# GaN_Schaltnetzteil.net
KiCad netlist of a schematic drawn in EAGLE
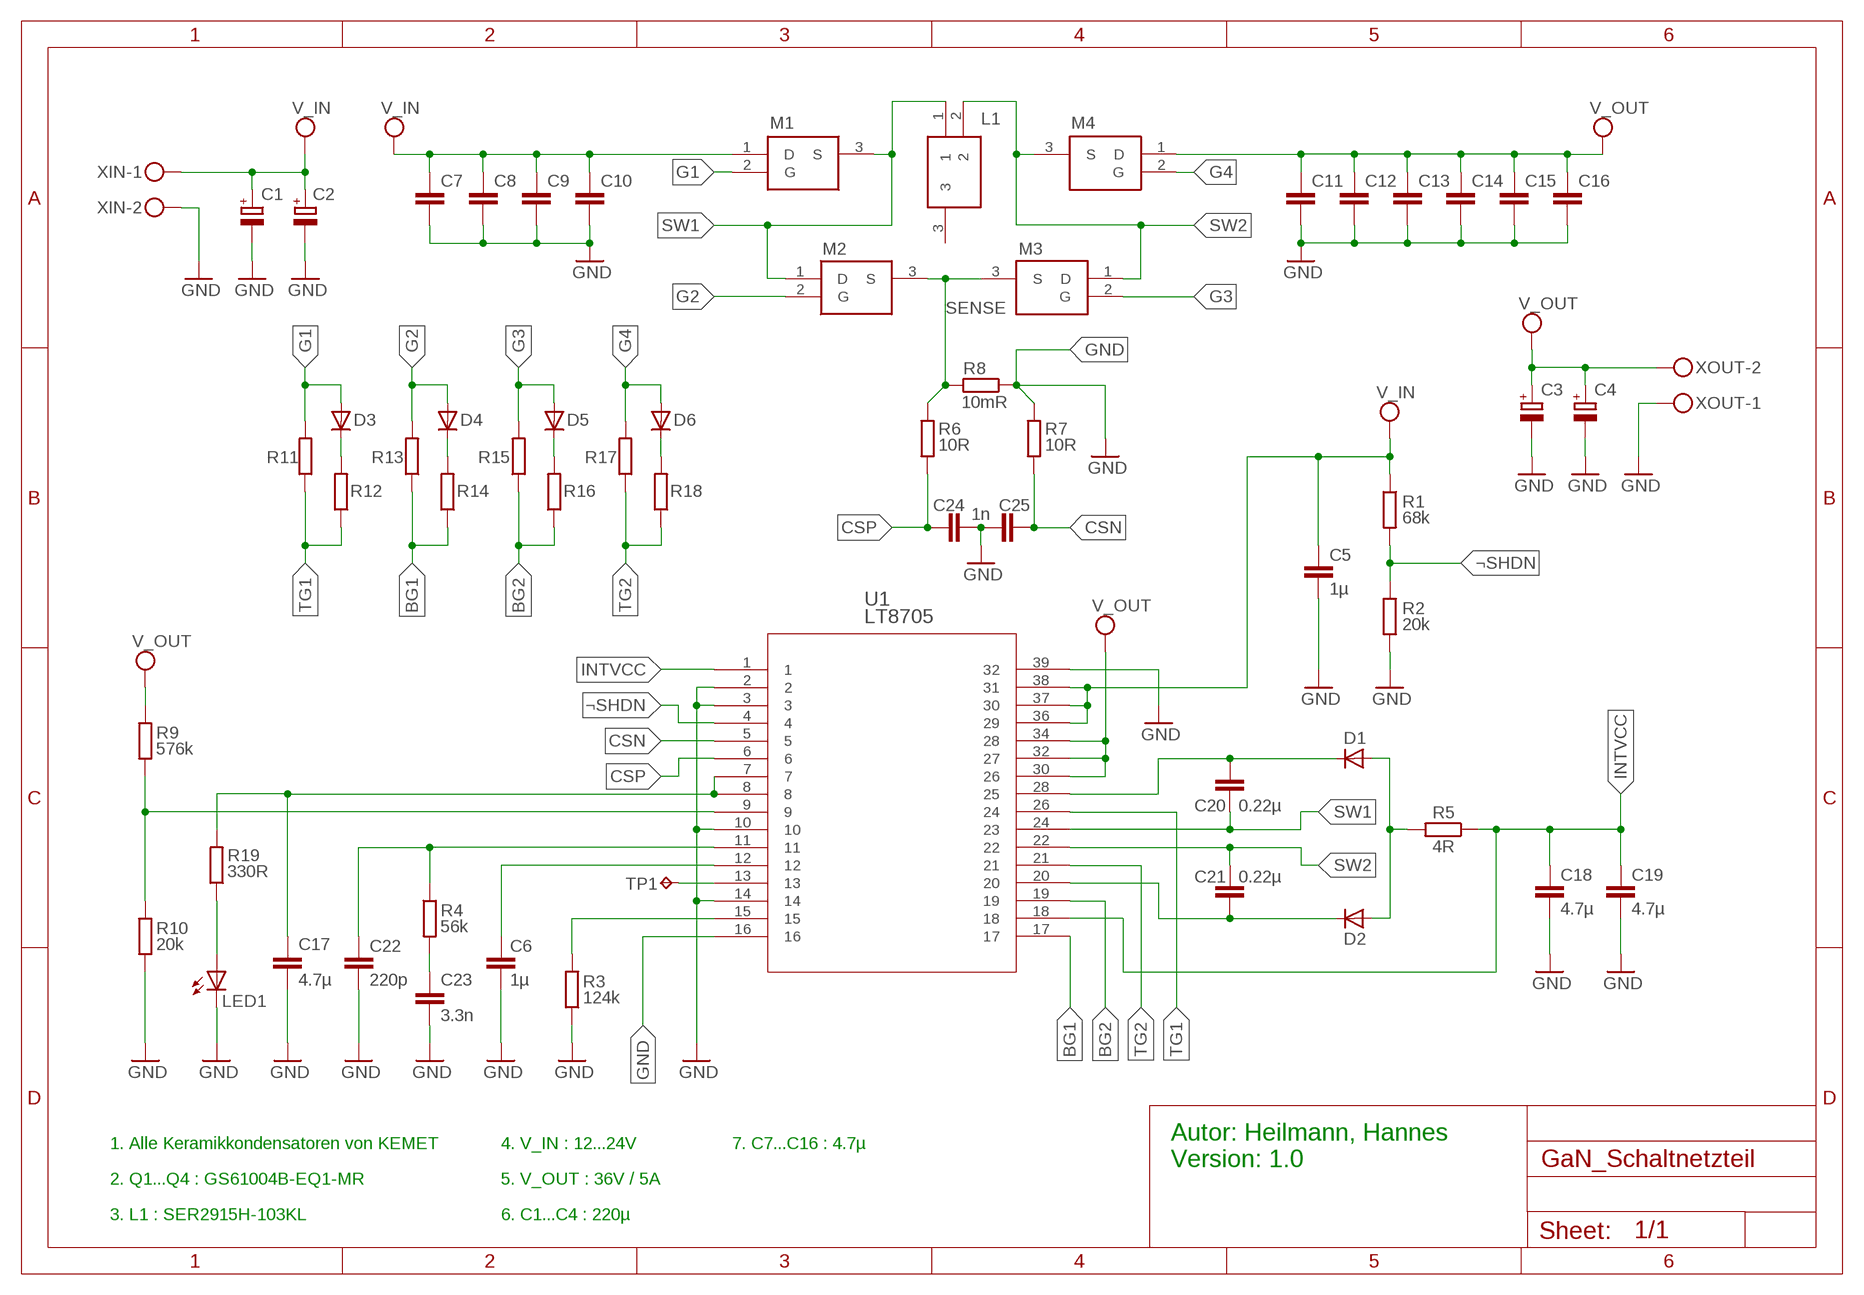
[diagram p0: schematic, sheet 1]

(export (version "E")
  (design (tool "Eeschema 10.0.6"))
  (components
    (comp (ref "C1")
      (value "220µ")
      (footprint "eagle-import:PANASONIC_G")
      (libsource (lib "eagle-import") (part "CPOL-EUG"))
    )
    (comp (ref "C2")
      (value "220µ")
      (footprint "eagle-import:PANASONIC_G")
      (libsource (lib "eagle-import") (part "CPOL-EUG"))
    )
    (comp (ref "C3")
      (value "220µ")
      (footprint "eagle-import:PANASONIC_G")
      (libsource (lib "eagle-import") (part "CPOL-EUG"))
    )
    (comp (ref "C4")
      (value "220µ")
      (footprint "eagle-import:PANASONIC_G")
      (libsource (lib "eagle-import") (part "CPOL-EUG"))
    )
    (comp (ref "C5")
      (value "1µ")
      (footprint "eagle-import:C1206K")
      (libsource (lib "eagle-import") (part "C-EUC1206K"))
    )
    (comp (ref "C6")
      (value "1µ")
      (footprint "eagle-import:C1206K")
      (libsource (lib "eagle-import") (part "C-EUC1206K"))
    )
    (comp (ref "C7")
      (value "4.7µ")
      (footprint "eagle-import:C1206K")
      (libsource (lib "eagle-import") (part "C-EUC1206K"))
    )
    (comp (ref "C8")
      (value "4.7µ")
      (footprint "eagle-import:C1206K")
      (libsource (lib "eagle-import") (part "C-EUC1206K"))
    )
    (comp (ref "C9")
      (value "4.7µ")
      (footprint "eagle-import:C1206K")
      (libsource (lib "eagle-import") (part "C-EUC1206K"))
    )
    (comp (ref "C10")
      (value "4.7µ")
      (footprint "eagle-import:C1206K")
      (libsource (lib "eagle-import") (part "C-EUC1206K"))
    )
    (comp (ref "C11")
      (value "4.7µ")
      (footprint "eagle-import:C1206K")
      (libsource (lib "eagle-import") (part "C-EUC1206K"))
    )
    (comp (ref "C12")
      (value "4.7µ")
      (footprint "eagle-import:C1206K")
      (libsource (lib "eagle-import") (part "C-EUC1206K"))
    )
    (comp (ref "C13")
      (value "4.7µ")
      (footprint "eagle-import:C1206K")
      (libsource (lib "eagle-import") (part "C-EUC1206K"))
    )
    (comp (ref "C14")
      (value "4.7µ")
      (footprint "eagle-import:C1206K")
      (libsource (lib "eagle-import") (part "C-EUC1206K"))
    )
    (comp (ref "C15")
      (value "4.7µ")
      (footprint "eagle-import:C1206K")
      (libsource (lib "eagle-import") (part "C-EUC1206K"))
    )
    (comp (ref "C16")
      (value "4.7µ")
      (footprint "eagle-import:C1206K")
      (libsource (lib "eagle-import") (part "C-EUC1206K"))
    )
    (comp (ref "C17")
      (value "4.7µ")
      (footprint "eagle-import:C1206K")
      (libsource (lib "eagle-import") (part "C-EUC1206K"))
    )
    (comp (ref "C18")
      (value "4.7µ")
      (footprint "eagle-import:C1206K")
      (libsource (lib "eagle-import") (part "C-EUC1206K"))
    )
    (comp (ref "C19")
      (value "4.7µ")
      (footprint "eagle-import:C1206K")
      (libsource (lib "eagle-import") (part "C-EUC1206K"))
    )
    (comp (ref "C20")
      (value "0.22µ")
      (footprint "eagle-import:C1206K")
      (libsource (lib "eagle-import") (part "C-EUC1206K"))
    )
    (comp (ref "C21")
      (value "0.22µ")
      (footprint "eagle-import:C1206K")
      (libsource (lib "eagle-import") (part "C-EUC1206K"))
    )
    (comp (ref "C22")
      (value "220p")
      (footprint "eagle-import:C1206K")
      (libsource (lib "eagle-import") (part "C-EUC1206K"))
    )
    (comp (ref "C23")
      (value "3.3n")
      (footprint "eagle-import:C1206K")
      (libsource (lib "eagle-import") (part "C-EUC1206K"))
    )
    (comp (ref "C24")
      (value "1n")
      (footprint "eagle-import:C1206K")
      (libsource (lib "eagle-import") (part "C-EUC1206K"))
    )
    (comp (ref "C25")
      (value "1n")
      (footprint "eagle-import:C1206K")
      (libsource (lib "eagle-import") (part "C-EUC1206K"))
    )
    (comp (ref "D1")
      (value "GF1")
      (footprint "eagle-import:SMA-DO214AC")
      (fields (field (name "SPICEPREFIX") "D"))
      (libsource (lib "eagle-import") (part "GF1"))
    )
    (comp (ref "D2")
      (value "GF1")
      (footprint "eagle-import:SMA-DO214AC")
      (libsource (lib "eagle-import") (part "GF1"))
    )
    (comp (ref "D3")
      (value "GF1")
      (footprint "eagle-import:SMA-DO214AC")
      (libsource (lib "eagle-import") (part "GF1"))
    )
    (comp (ref "D4")
      (value "GF1")
      (footprint "eagle-import:SMA-DO214AC")
      (libsource (lib "eagle-import") (part "GF1"))
    )
    (comp (ref "D5")
      (value "GF1")
      (footprint "eagle-import:SMA-DO214AC")
      (libsource (lib "eagle-import") (part "GF1"))
    )
    (comp (ref "D6")
      (value "GF1")
      (footprint "eagle-import:SMA-DO214AC")
      (libsource (lib "eagle-import") (part "GF1"))
    )
    (comp (ref "L1")
      (value "SER2915H-103KL")
      (footprint "eagle-import:SER2900")
      (fields (field (name "FARNELL_PART_NUMBER") "2288897"))
      (libsource (lib "eagle-import") (part "SER2915H-103KL"))
    )
    (comp (ref "LED1")
      (value "LEDSMT1206")
      (footprint "eagle-import:1206")
      (libsource (lib "eagle-import") (part "LEDSMT1206"))
    )
    (comp (ref "M1")
      (value "GS61004B-E01-MR")
      (footprint "eagle-import:GS61004B-E01-MR")
      (fields (field (name "MOUSER_PART_NUMBER") "499-GS61004B-E01-MR"))
      (libsource (lib "eagle-import") (part "GS61004B-E01-MR"))
    )
    (comp (ref "M2")
      (value "GS61004B-E01-MR")
      (footprint "eagle-import:GS61004B-E01-MR")
      (fields (field (name "MOUSER_PART_NUMBER") "499-GS61004B-E01-MR"))
      (libsource (lib "eagle-import") (part "GS61004B-E01-MR"))
    )
    (comp (ref "M3")
      (value "GS61004B-E01-MR")
      (footprint "eagle-import:GS61004B-E01-MR")
      (fields (field (name "MOUSER_PART_NUMBER") "499-GS61004B-E01-MR"))
      (libsource (lib "eagle-import") (part "GS61004B-E01-MR"))
    )
    (comp (ref "M4")
      (value "GS61004B-E01-MR")
      (footprint "eagle-import:GS61004B-E01-MR")
      (fields (field (name "MOUSER_PART_NUMBER") "499-GS61004B-E01-MR"))
      (libsource (lib "eagle-import") (part "GS61004B-E01-MR"))
    )
    (comp (ref "R1")
      (value "68k")
      (footprint "eagle-import:R1206")
      (libsource (lib "eagle-import") (part "R-EU_R1206"))
    )
    (comp (ref "R2")
      (value "20k")
      (footprint "eagle-import:R1206")
      (libsource (lib "eagle-import") (part "R-EU_R1206"))
    )
    (comp (ref "R3")
      (value "124k")
      (footprint "eagle-import:R1206")
      (libsource (lib "eagle-import") (part "R-EU_R1206"))
    )
    (comp (ref "R4")
      (value "56k")
      (footprint "eagle-import:R1206")
      (libsource (lib "eagle-import") (part "R-EU_R1206"))
    )
    (comp (ref "R5")
      (value "4R")
      (footprint "eagle-import:R1206")
      (libsource (lib "eagle-import") (part "R-EU_R1206"))
    )
    (comp (ref "R6")
      (value "10R")
      (footprint "eagle-import:R1206")
      (libsource (lib "eagle-import") (part "R-EU_R1206"))
    )
    (comp (ref "R7")
      (value "10R")
      (footprint "eagle-import:R1206")
      (libsource (lib "eagle-import") (part "R-EU_R1206"))
    )
    (comp (ref "R8")
      (value "10mR")
      (footprint "eagle-import:R1206")
      (libsource (lib "eagle-import") (part "R-EU_R1206"))
    )
    (comp (ref "R9")
      (value "576k")
      (footprint "eagle-import:R1206")
      (libsource (lib "eagle-import") (part "R-EU_R1206"))
    )
    (comp (ref "R10")
      (value "20k")
      (footprint "eagle-import:R1206")
      (libsource (lib "eagle-import") (part "R-EU_R1206"))
    )
    (comp (ref "R11")
      (value "R-EU_R1206")
      (footprint "eagle-import:R1206")
      (libsource (lib "eagle-import") (part "R-EU_R1206"))
    )
    (comp (ref "R12")
      (value "R-EU_R1206")
      (footprint "eagle-import:R1206")
      (libsource (lib "eagle-import") (part "R-EU_R1206"))
    )
    (comp (ref "R13")
      (value "R-EU_R1206")
      (footprint "eagle-import:R1206")
      (libsource (lib "eagle-import") (part "R-EU_R1206"))
    )
    (comp (ref "R14")
      (value "R-EU_R1206")
      (footprint "eagle-import:R1206")
      (libsource (lib "eagle-import") (part "R-EU_R1206"))
    )
    (comp (ref "R15")
      (value "R-EU_R1206")
      (footprint "eagle-import:R1206")
      (libsource (lib "eagle-import") (part "R-EU_R1206"))
    )
    (comp (ref "R16")
      (value "R-EU_R1206")
      (footprint "eagle-import:R1206")
      (libsource (lib "eagle-import") (part "R-EU_R1206"))
    )
    (comp (ref "R17")
      (value "R-EU_R1206")
      (footprint "eagle-import:R1206")
      (libsource (lib "eagle-import") (part "R-EU_R1206"))
    )
    (comp (ref "R18")
      (value "R-EU_R1206")
      (footprint "eagle-import:R1206")
      (libsource (lib "eagle-import") (part "R-EU_R1206"))
    )
    (comp (ref "R19")
      (value "330R")
      (footprint "eagle-import:R1206")
      (libsource (lib "eagle-import") (part "R-EU_R1206"))
    )
    (comp (ref "TP1")
      (value "TPTP08R")
      (footprint "eagle-import:TP08R")
      (libsource (lib "eagle-import") (part "TPTP08R"))
    )
    (comp (ref "U1")
      (value "LT8705")
      (footprint "eagle-import:TSSOP-38_FE_AB")
      (libsource (lib "eagle-import") (part "LT8705"))
    )
    (comp (ref "XIN")
      (value "INPUT")
      (footprint "eagle-import:W237-102")
      (fields (field (name "MPN") "237-102"))
      (libsource (lib "eagle-import") (part "W237-102"))
    )
    (comp (ref "XOUT")
      (value "OUTPUT")
      (footprint "eagle-import:W237-102")
      (fields (field (name "MPN") "237-102"))
      (libsource (lib "eagle-import") (part "W237-102"))
    )
  )
  (nets
    (net (code "1") (name "/SENSE") (class "Default")
      (node (ref "M2") (pin "3") (pinfunction "S_3") (pintype "bidirectional"))
      (node (ref "M3") (pin "3") (pinfunction "S_3") (pintype "bidirectional"))
      (node (ref "R6") (pin "2") (pinfunction "2_2") (pintype "passive"))
      (node (ref "R8") (pin "2") (pinfunction "2_2") (pintype "passive"))
    )
    (net (code "2") (name "BG1") (class "Default")
      (node (ref "R13") (pin "1") (pinfunction "1_1") (pintype "passive"))
      (node (ref "R14") (pin "1") (pinfunction "1_1") (pintype "passive"))
      (node (ref "U1") (pin "17") (pinfunction "17_17") (pintype "passive"))
    )
    (net (code "3") (name "BG2") (class "Default")
      (node (ref "R15") (pin "1") (pinfunction "1_1") (pintype "passive"))
      (node (ref "R16") (pin "1") (pinfunction "1_1") (pintype "passive"))
      (node (ref "U1") (pin "19") (pinfunction "19_19") (pintype "passive"))
    )
    (net (code "4") (name "CSN") (class "Default")
      (node (ref "C25") (pin "2") (pinfunction "2_2") (pintype "passive"))
      (node (ref "R7") (pin "1") (pinfunction "1_1") (pintype "passive"))
      (node (ref "U1") (pin "5") (pinfunction "5_5") (pintype "passive"))
    )
    (net (code "5") (name "CSP") (class "Default")
      (node (ref "C24") (pin "1") (pinfunction "1_1") (pintype "passive"))
      (node (ref "R6") (pin "1") (pinfunction "1_1") (pintype "passive"))
      (node (ref "U1") (pin "6") (pinfunction "6_6") (pintype "passive"))
    )
    (net (code "6") (name "G1") (class "Default")
      (node (ref "D3") (pin "A") (pinfunction "A_A") (pintype "passive"))
      (node (ref "M1") (pin "2") (pinfunction "G_2") (pintype "bidirectional"))
      (node (ref "R11") (pin "2") (pinfunction "2_2") (pintype "passive"))
    )
    (net (code "7") (name "G2") (class "Default")
      (node (ref "D4") (pin "A") (pinfunction "A_A") (pintype "passive"))
      (node (ref "M2") (pin "2") (pinfunction "G_2") (pintype "bidirectional"))
      (node (ref "R13") (pin "2") (pinfunction "2_2") (pintype "passive"))
    )
    (net (code "8") (name "G3") (class "Default")
      (node (ref "D5") (pin "A") (pinfunction "A_A") (pintype "passive"))
      (node (ref "M3") (pin "2") (pinfunction "G_2") (pintype "bidirectional"))
      (node (ref "R15") (pin "2") (pinfunction "2_2") (pintype "passive"))
    )
    (net (code "9") (name "G4") (class "Default")
      (node (ref "D6") (pin "A") (pinfunction "A_A") (pintype "passive"))
      (node (ref "M4") (pin "2") (pinfunction "G_2") (pintype "bidirectional"))
      (node (ref "R17") (pin "2") (pinfunction "2_2") (pintype "passive"))
    )
    (net (code "10") (name "GND") (class "Default")
      (node (ref "C1") (pin "-") (pinfunction "-_-") (pintype "passive"))
      (node (ref "C10") (pin "2") (pinfunction "2_2") (pintype "passive"))
      (node (ref "C11") (pin "2") (pinfunction "2_2") (pintype "passive"))
      (node (ref "C12") (pin "2") (pinfunction "2_2") (pintype "passive"))
      (node (ref "C13") (pin "2") (pinfunction "2_2") (pintype "passive"))
      (node (ref "C14") (pin "2") (pinfunction "2_2") (pintype "passive"))
      (node (ref "C15") (pin "2") (pinfunction "2_2") (pintype "passive"))
      (node (ref "C16") (pin "2") (pinfunction "2_2") (pintype "passive"))
      (node (ref "C17") (pin "2") (pinfunction "2_2") (pintype "passive"))
      (node (ref "C18") (pin "2") (pinfunction "2_2") (pintype "passive"))
      (node (ref "C19") (pin "2") (pinfunction "2_2") (pintype "passive"))
      (node (ref "C2") (pin "-") (pinfunction "-_-") (pintype "passive"))
      (node (ref "C22") (pin "2") (pinfunction "2_2") (pintype "passive"))
      (node (ref "C23") (pin "2") (pinfunction "2_2") (pintype "passive"))
      (node (ref "C24") (pin "2") (pinfunction "2_2") (pintype "passive"))
      (node (ref "C25") (pin "1") (pinfunction "1_1") (pintype "passive"))
      (node (ref "C3") (pin "-") (pinfunction "-_-") (pintype "passive"))
      (node (ref "C4") (pin "-") (pinfunction "-_-") (pintype "passive"))
      (node (ref "C5") (pin "2") (pinfunction "2_2") (pintype "passive"))
      (node (ref "C6") (pin "2") (pinfunction "2_2") (pintype "passive"))
      (node (ref "C7") (pin "2") (pinfunction "2_2") (pintype "passive"))
      (node (ref "C8") (pin "2") (pinfunction "2_2") (pintype "passive"))
      (node (ref "C9") (pin "2") (pinfunction "2_2") (pintype "passive"))
      (node (ref "LED1") (pin "C") (pinfunction "C_C") (pintype "passive"))
      (node (ref "R10") (pin "2") (pinfunction "2_2") (pintype "passive"))
      (node (ref "R2") (pin "2") (pinfunction "2_2") (pintype "passive"))
      (node (ref "R3") (pin "1") (pinfunction "1_1") (pintype "passive"))
      (node (ref "R7") (pin "2") (pinfunction "2_2") (pintype "passive"))
      (node (ref "R8") (pin "1") (pinfunction "1_1") (pintype "passive"))
      (node (ref "U1") (pin "10") (pinfunction "10_10") (pintype "passive"))
      (node (ref "U1") (pin "14") (pinfunction "14_14") (pintype "passive"))
      (node (ref "U1") (pin "16") (pinfunction "16_16") (pintype "passive"))
      (node (ref "U1") (pin "2") (pinfunction "2_2") (pintype "passive"))
      (node (ref "U1") (pin "3") (pinfunction "3_3") (pintype "passive"))
      (node (ref "U1") (pin "39") (pinfunction "32_39") (pintype "passive"))
      (node (ref "XIN") (pin "2") (pinfunction "KL_2") (pintype "passive"))
      (node (ref "XOUT") (pin "1") (pinfunction "KL_1") (pintype "passive"))
    )
    (net (code "11") (name "INTVCC") (class "Default")
      (node (ref "C18") (pin "1") (pinfunction "1_1") (pintype "passive"))
      (node (ref "C19") (pin "1") (pinfunction "1_1") (pintype "passive"))
      (node (ref "R5") (pin "1") (pinfunction "1_1") (pintype "passive"))
      (node (ref "U1") (pin "1") (pinfunction "1_1") (pintype "passive"))
      (node (ref "U1") (pin "18") (pinfunction "18_18") (pintype "passive"))
    )
    (net (code "12") (name "Net-(C6-Pad1)") (class "Default")
      (node (ref "C6") (pin "1") (pinfunction "1_1") (pintype "passive"))
      (node (ref "U1") (pin "12") (pinfunction "12_12") (pintype "passive"))
    )
    (net (code "13") (name "Net-(C17-Pad1)") (class "Default")
      (node (ref "C17") (pin "1") (pinfunction "1_1") (pintype "passive"))
      (node (ref "R19") (pin "2") (pinfunction "2_2") (pintype "passive"))
      (node (ref "U1") (pin "7") (pinfunction "7_7") (pintype "passive"))
      (node (ref "U1") (pin "8") (pinfunction "8_8") (pintype "passive"))
    )
    (net (code "14") (name "Net-(C22-Pad1)") (class "Default")
      (node (ref "C22") (pin "1") (pinfunction "1_1") (pintype "passive"))
      (node (ref "R4") (pin "1") (pinfunction "1_1") (pintype "passive"))
      (node (ref "U1") (pin "11") (pinfunction "11_11") (pintype "passive"))
    )
    (net (code "15") (name "Net-(C23-Pad1)") (class "Default")
      (node (ref "C23") (pin "1") (pinfunction "1_1") (pintype "passive"))
      (node (ref "R4") (pin "2") (pinfunction "2_2") (pintype "passive"))
    )
    (net (code "16") (name "Net-(D1-C)") (class "Default")
      (node (ref "C20") (pin "1") (pinfunction "1_1") (pintype "passive"))
      (node (ref "D1") (pin "K") (pinfunction "C_K") (pintype "passive"))
      (node (ref "U1") (pin "28") (pinfunction "25_28") (pintype "passive"))
    )
    (net (code "17") (name "Net-(D1-PadA)") (class "Default")
      (node (ref "D1") (pin "A") (pinfunction "A_A") (pintype "passive"))
      (node (ref "D2") (pin "A") (pinfunction "A_A") (pintype "passive"))
      (node (ref "R5") (pin "2") (pinfunction "2_2") (pintype "passive"))
    )
    (net (code "18") (name "Net-(D2-C)") (class "Default")
      (node (ref "C21") (pin "1") (pinfunction "1_1") (pintype "passive"))
      (node (ref "D2") (pin "K") (pinfunction "C_K") (pintype "passive"))
      (node (ref "U1") (pin "20") (pinfunction "20_20") (pintype "passive"))
    )
    (net (code "19") (name "Net-(D3-C)") (class "Default")
      (node (ref "D3") (pin "K") (pinfunction "C_K") (pintype "passive"))
      (node (ref "R12") (pin "2") (pinfunction "2_2") (pintype "passive"))
    )
    (net (code "20") (name "Net-(D4-C)") (class "Default")
      (node (ref "D4") (pin "K") (pinfunction "C_K") (pintype "passive"))
      (node (ref "R14") (pin "2") (pinfunction "2_2") (pintype "passive"))
    )
    (net (code "21") (name "Net-(D5-C)") (class "Default")
      (node (ref "D5") (pin "K") (pinfunction "C_K") (pintype "passive"))
      (node (ref "R16") (pin "2") (pinfunction "2_2") (pintype "passive"))
    )
    (net (code "22") (name "Net-(D6-C)") (class "Default")
      (node (ref "D6") (pin "K") (pinfunction "C_K") (pintype "passive"))
      (node (ref "R18") (pin "2") (pinfunction "2_2") (pintype "passive"))
    )
    (net (code "23") (name "Net-(LED1-PadA)") (class "Default")
      (node (ref "LED1") (pin "A") (pinfunction "A_A") (pintype "passive"))
      (node (ref "R19") (pin "1") (pinfunction "1_1") (pintype "passive"))
    )
    (net (code "24") (name "Net-(R3-Pad2)") (class "Default")
      (node (ref "R3") (pin "2") (pinfunction "2_2") (pintype "passive"))
      (node (ref "U1") (pin "15") (pinfunction "15_15") (pintype "passive"))
    )
    (net (code "25") (name "Net-(R10-Pad1)") (class "Default")
      (node (ref "R10") (pin "1") (pinfunction "1_1") (pintype "passive"))
      (node (ref "R9") (pin "2") (pinfunction "2_2") (pintype "passive"))
      (node (ref "U1") (pin "9") (pinfunction "9_9") (pintype "passive"))
    )
    (net (code "26") (name "Net-(TP1-PadTP)") (class "Default")
      (node (ref "TP1") (pin "TP") (pinfunction "TP_TP") (pintype "input"))
      (node (ref "U1") (pin "13") (pinfunction "13_13") (pintype "passive"))
    )
    (net (code "27") (name "SW1") (class "Default")
      (node (ref "C20") (pin "2") (pinfunction "2_2") (pintype "passive"))
      (node (ref "L1") (pin "1") (pinfunction "1_1") (pintype "bidirectional"))
      (node (ref "M1") (pin "3") (pinfunction "S_3") (pintype "bidirectional"))
      (node (ref "M2") (pin "1") (pinfunction "D_1") (pintype "bidirectional"))
      (node (ref "U1") (pin "24") (pinfunction "23_24") (pintype "passive"))
    )
    (net (code "28") (name "SW2") (class "Default")
      (node (ref "C21") (pin "2") (pinfunction "2_2") (pintype "passive"))
      (node (ref "L1") (pin "2") (pinfunction "2_2") (pintype "bidirectional"))
      (node (ref "M3") (pin "1") (pinfunction "D_1") (pintype "bidirectional"))
      (node (ref "M4") (pin "3") (pinfunction "S_3") (pintype "bidirectional"))
      (node (ref "U1") (pin "22") (pinfunction "22_22") (pintype "passive"))
    )
    (net (code "29") (name "TG1") (class "Default")
      (node (ref "R11") (pin "1") (pinfunction "1_1") (pintype "passive"))
      (node (ref "R12") (pin "1") (pinfunction "1_1") (pintype "passive"))
      (node (ref "U1") (pin "26") (pinfunction "24_26") (pintype "passive"))
    )
    (net (code "30") (name "TG2") (class "Default")
      (node (ref "R17") (pin "1") (pinfunction "1_1") (pintype "passive"))
      (node (ref "R18") (pin "1") (pinfunction "1_1") (pintype "passive"))
      (node (ref "U1") (pin "21") (pinfunction "21_21") (pintype "passive"))
    )
    (net (code "31") (name "V_IN") (class "Default")
      (node (ref "C1") (pin "+") (pinfunction "+_+") (pintype "passive"))
      (node (ref "C10") (pin "1") (pinfunction "1_1") (pintype "passive"))
      (node (ref "C2") (pin "+") (pinfunction "+_+") (pintype "passive"))
      (node (ref "C5") (pin "1") (pinfunction "1_1") (pintype "passive"))
      (node (ref "C7") (pin "1") (pinfunction "1_1") (pintype "passive"))
      (node (ref "C8") (pin "1") (pinfunction "1_1") (pintype "passive"))
      (node (ref "C9") (pin "1") (pinfunction "1_1") (pintype "passive"))
      (node (ref "M1") (pin "1") (pinfunction "D_1") (pintype "bidirectional"))
      (node (ref "R1") (pin "1") (pinfunction "1_1") (pintype "passive"))
      (node (ref "U1") (pin "36") (pinfunction "29_36") (pintype "passive"))
      (node (ref "U1") (pin "37") (pinfunction "30_37") (pintype "passive"))
      (node (ref "U1") (pin "38") (pinfunction "31_38") (pintype "passive"))
      (node (ref "XIN") (pin "1") (pinfunction "KL_1") (pintype "passive"))
    )
    (net (code "32") (name "V_OUT") (class "Default")
      (node (ref "C11") (pin "1") (pinfunction "1_1") (pintype "passive"))
      (node (ref "C12") (pin "1") (pinfunction "1_1") (pintype "passive"))
      (node (ref "C13") (pin "1") (pinfunction "1_1") (pintype "passive"))
      (node (ref "C14") (pin "1") (pinfunction "1_1") (pintype "passive"))
      (node (ref "C15") (pin "1") (pinfunction "1_1") (pintype "passive"))
      (node (ref "C16") (pin "1") (pinfunction "1_1") (pintype "passive"))
      (node (ref "C3") (pin "+") (pinfunction "+_+") (pintype "passive"))
      (node (ref "C4") (pin "+") (pinfunction "+_+") (pintype "passive"))
      (node (ref "M4") (pin "1") (pinfunction "D_1") (pintype "bidirectional"))
      (node (ref "R9") (pin "1") (pinfunction "1_1") (pintype "passive"))
      (node (ref "U1") (pin "30") (pinfunction "26_30") (pintype "passive"))
      (node (ref "U1") (pin "32") (pinfunction "27_32") (pintype "passive"))
      (node (ref "U1") (pin "34") (pinfunction "28_34") (pintype "passive"))
      (node (ref "XOUT") (pin "2") (pinfunction "KL_2") (pintype "passive"))
    )
    (net (code "33") (name "unconnected-(L1-Pad3)") (class "Default")
      (node (ref "L1") (pin "3") (pinfunction "3_3") (pintype "bidirectional"))
    )
    (net (code "34") (name "¬SHDN") (class "Default")
      (node (ref "R1") (pin "2") (pinfunction "2_2") (pintype "passive"))
      (node (ref "R2") (pin "1") (pinfunction "1_1") (pintype "passive"))
      (node (ref "U1") (pin "4") (pinfunction "4_4") (pintype "passive"))
    )
  )
)
